# Peripherals_Main_Board.net
KiCad netlist of a schematic drawn in Altium Designer
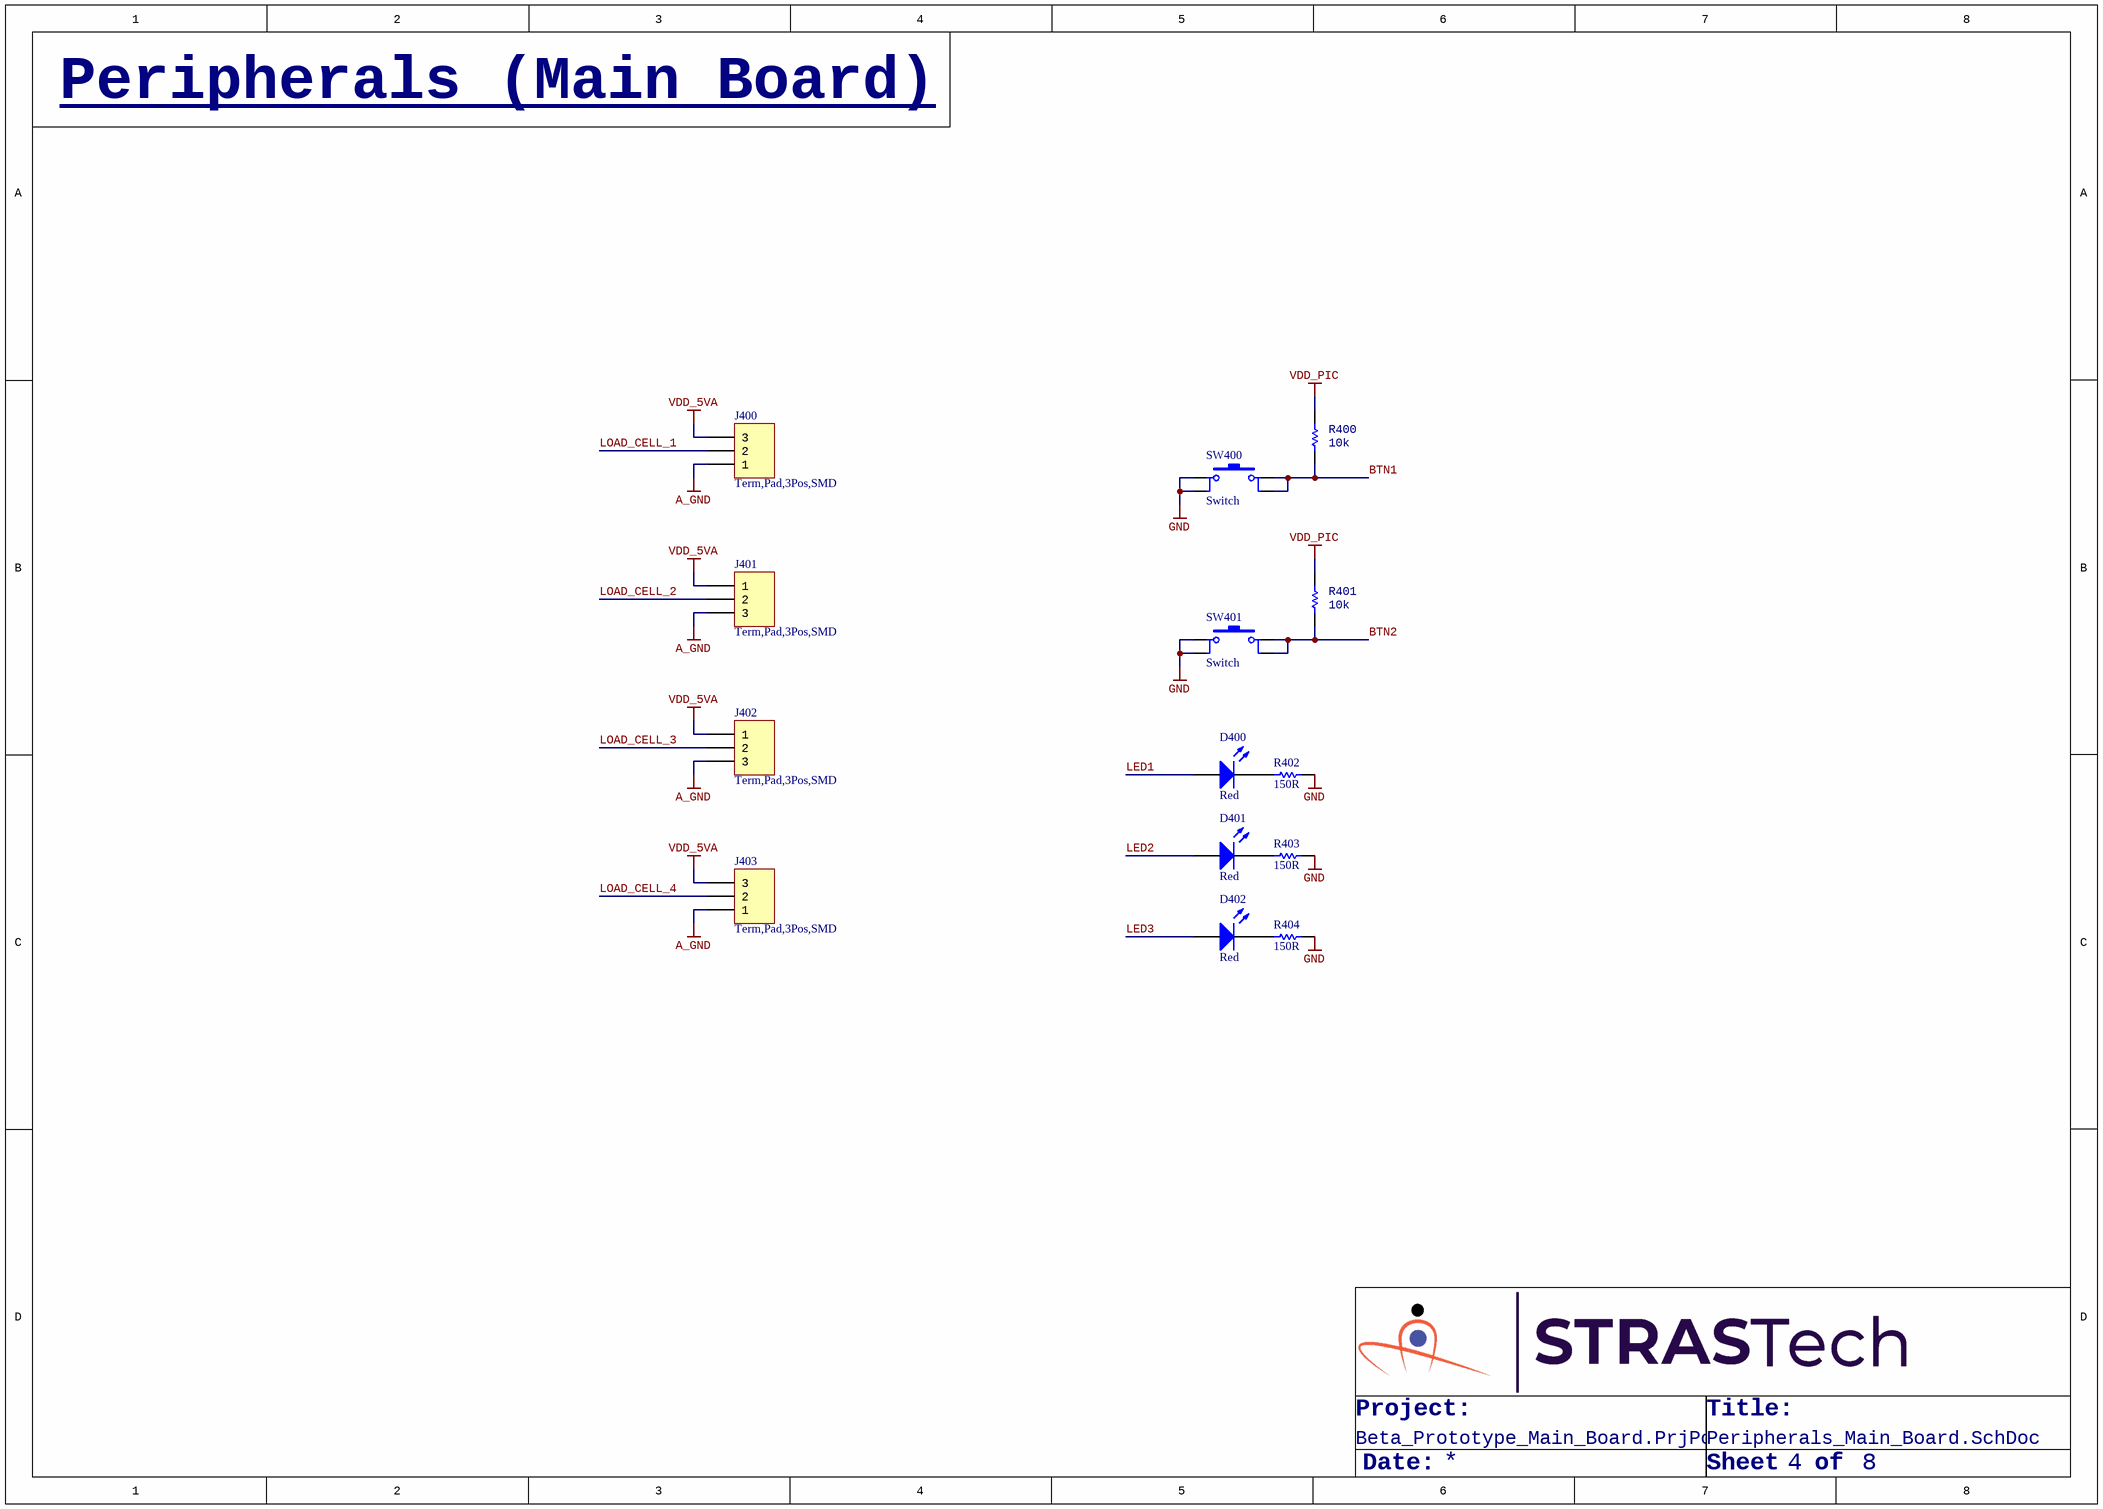
[diagram p0: Peripherals_Main_Board.SchDoc]

(export (version "E")
  (design (tool "Eeschema 10.0.6"))
  (components
    (comp (ref "D400")
      (value "Red")
      (footprint "LED,5mm,Thru")
      (description "Red 623nm LED Indication - Discrete 2V Radial")
      (fields
        (field (name "MANUFACTURER") "TT Electronics/Optek Technology")
        (field (name "MANUFACTURER PART NUMBER") "OVLFR3C7")
        (field (name "CREATEDBY") "Judd Foster")
      )
      (libsource (lib "symbols") (part "LED,Red,5mm,Thru"))
    )
    (comp (ref "D401")
      (value "Red")
      (footprint "LED,5mm,Thru")
      (description "Red 623nm LED Indication - Discrete 2V Radial")
      (fields
        (field (name "MANUFACTURER") "TT Electronics/Optek Technology")
        (field (name "MANUFACTURER PART NUMBER") "OVLFR3C7")
        (field (name "CREATEDBY") "Judd Foster")
      )
      (libsource (lib "symbols") (part "LED,Red,5mm,Thru"))
    )
    (comp (ref "D402")
      (value "Red")
      (footprint "LED,5mm,Thru")
      (description "Red 623nm LED Indication - Discrete 2V Radial")
      (fields
        (field (name "MANUFACTURER") "TT Electronics/Optek Technology")
        (field (name "MANUFACTURER PART NUMBER") "OVLFR3C7")
        (field (name "CREATEDBY") "Judd Foster")
      )
      (libsource (lib "symbols") (part "LED,Red,5mm,Thru"))
    )
    (comp (ref "J400")
      (value "Term,Pad,3Pos,SMD")
      (footprint "Term,Pad,3Pos,SMD")
      (description "SMD pads for soldering wires with strain relief")
      (fields (field (name "CREATED BY") "Judd Foster"))
      (libsource (lib "") (part "Term,Pad,3Pos,SMD_1"))
    )
    (comp (ref "J401")
      (value "Term,Pad,3Pos,SMD")
      (footprint "Term,Pad,3Pos,SMD")
      (description "SMD pads for soldering wires with strain relief")
      (fields (field (name "CREATED BY") "Judd Foster"))
      (libsource (lib "symbols") (part "Term,Pad,3Pos,SMD"))
    )
    (comp (ref "J402")
      (value "Term,Pad,3Pos,SMD")
      (footprint "Term,Pad,3Pos,SMD")
      (description "SMD pads for soldering wires with strain relief")
      (fields (field (name "CREATED BY") "Judd Foster"))
      (libsource (lib "symbols") (part "Term,Pad,3Pos,SMD"))
    )
    (comp (ref "J403")
      (value "Term,Pad,3Pos,SMD")
      (footprint "Term,Pad,3Pos,SMD")
      (description "SMD pads for soldering wires with strain relief")
      (fields (field (name "CREATED BY") "Judd Foster"))
      (libsource (lib "") (part "Term,Pad,3Pos,SMD_1"))
    )
    (comp (ref "R400")
      (value "10k")
      (footprint "RES,0402")
      (description "10 kOhms ±5% 0.063W, 1/16W Chip Resistor 0402 (1005 Metric) Automotive AEC-Q200 Thick Film")
      (fields
        (field (name "VENDOR PART NUMBER") "RMCF0402JT10K0CT-ND")
        (field (name "MANUFACTURER") "Stackpole Electronics Inc")
        (field (name "CREATEDBY") "Judd Foster")
      )
      (libsource (lib "symbols") (part "RES,10k,5%,0.063W,0402"))
    )
    (comp (ref "R401")
      (value "10k")
      (footprint "RES,0402")
      (description "10 kOhms ±5% 0.063W, 1/16W Chip Resistor 0402 (1005 Metric) Automotive AEC-Q200 Thick Film")
      (fields
        (field (name "VENDOR PART NUMBER") "RMCF0402JT10K0CT-ND")
        (field (name "MANUFACTURER") "Stackpole Electronics Inc")
        (field (name "CREATEDBY") "Judd Foster")
      )
      (libsource (lib "symbols") (part "RES,10k,5%,0.063W,0402"))
    )
    (comp (ref "R402")
      (value "150R")
      (footprint "RES,0402")
      (fields
        (field (name "MANUFACTURER") "TE Connectivity Passive Product")
        (field (name "MANUFACTURER PART NUMBER") "CRGCQ0402F150R")
        (field (name "VENDOR PART NUMBER") "A129617CT-ND")
        (field (name "CREATEDBY") "Judd Foster")
      )
      (libsource (lib "symbols") (part "RES,150R,1%,0.1W,0402"))
    )
    (comp (ref "R403")
      (value "150R")
      (footprint "RES,0402")
      (fields
        (field (name "MANUFACTURER") "TE Connectivity Passive Product")
        (field (name "MANUFACTURER PART NUMBER") "CRGCQ0402F150R")
        (field (name "VENDOR PART NUMBER") "A129617CT-ND")
        (field (name "CREATEDBY") "Judd Foster")
      )
      (libsource (lib "symbols") (part "RES,150R,1%,0.1W,0402"))
    )
    (comp (ref "R404")
      (value "150R")
      (footprint "RES,0402")
      (fields
        (field (name "MANUFACTURER") "TE Connectivity Passive Product")
        (field (name "MANUFACTURER PART NUMBER") "CRGCQ0402F150R")
        (field (name "VENDOR PART NUMBER") "A129617CT-ND")
        (field (name "CREATEDBY") "Judd Foster")
      )
      (libsource (lib "symbols") (part "RES,150R,1%,0.1W,0402"))
    )
    (comp (ref "SW400")
      (value "Switch")
      (footprint "Switch,Tactile,SPST-NO,SMD")
      (description "Tactile Switch SPST-NO Top Actuated Surface Mount")
      (fields
        (field (name "MANUFACTURER") "C&K")
        (field (name "MANUFACTURER PART NUMBER") "PTS645SK50SMTR92 LFS")
        (field (name "CREATEDBY") "Judd Foster")
      )
      (libsource (lib "symbols") (part "Switch,Tactile,SPST-NO,SMD,H5.0"))
    )
    (comp (ref "SW401")
      (value "Switch")
      (footprint "Switch,Tactile,SPST-NO,SMD")
      (description "Tactile Switch SPST-NO Top Actuated Surface Mount")
      (fields
        (field (name "MANUFACTURER") "C&K")
        (field (name "MANUFACTURER PART NUMBER") "PTS645SK50SMTR92 LFS")
        (field (name "CREATEDBY") "Judd Foster")
      )
      (libsource (lib "symbols") (part "Switch,Tactile,SPST-NO,SMD,H5.0"))
    )
  )
  (nets
    (net (code "1") (name "/BTN1") (class "Default")
      (node (ref "R400") (pin "2") (pinfunction "2_2") (pintype "passive"))
      (node (ref "SW400") (pin "3") (pinfunction "3_3") (pintype "passive"))
      (node (ref "SW400") (pin "4") (pinfunction "4_4") (pintype "passive"))
    )
    (net (code "2") (name "/BTN2") (class "Default")
      (node (ref "R401") (pin "2") (pinfunction "2_2") (pintype "passive"))
      (node (ref "SW401") (pin "3") (pinfunction "3_3") (pintype "passive"))
      (node (ref "SW401") (pin "4") (pinfunction "4_4") (pintype "passive"))
    )
    (net (code "3") (name "/LED1") (class "Default")
      (node (ref "D400") (pin "1") (pinfunction "A_1") (pintype "passive"))
    )
    (net (code "4") (name "/LED2") (class "Default")
      (node (ref "D401") (pin "1") (pinfunction "A_1") (pintype "passive"))
    )
    (net (code "5") (name "/LED3") (class "Default")
      (node (ref "D402") (pin "1") (pinfunction "A_1") (pintype "passive"))
    )
    (net (code "6") (name "/LOAD_CELL_1") (class "Default")
      (node (ref "J400") (pin "2") (pinfunction "2_2") (pintype "passive"))
    )
    (net (code "7") (name "/LOAD_CELL_2") (class "Default")
      (node (ref "J401") (pin "2") (pinfunction "2_2") (pintype "passive"))
    )
    (net (code "8") (name "/LOAD_CELL_3") (class "Default")
      (node (ref "J402") (pin "2") (pinfunction "2_2") (pintype "passive"))
    )
    (net (code "9") (name "/LOAD_CELL_4") (class "Default")
      (node (ref "J403") (pin "2") (pinfunction "2_2") (pintype "passive"))
    )
    (net (code "10") (name "A_GND") (class "Default")
      (node (ref "J400") (pin "1") (pinfunction "1_1") (pintype "passive"))
      (node (ref "J401") (pin "3") (pinfunction "3_3") (pintype "passive"))
      (node (ref "J402") (pin "3") (pinfunction "3_3") (pintype "passive"))
      (node (ref "J403") (pin "1") (pinfunction "1_1") (pintype "passive"))
    )
    (net (code "11") (name "GND") (class "Default")
      (node (ref "R402") (pin "2") (pinfunction "2_2") (pintype "passive"))
      (node (ref "R403") (pin "2") (pinfunction "2_2") (pintype "passive"))
      (node (ref "R404") (pin "2") (pinfunction "2_2") (pintype "passive"))
      (node (ref "SW400") (pin "1") (pinfunction "1_1") (pintype "passive"))
      (node (ref "SW400") (pin "2") (pinfunction "2_2") (pintype "passive"))
      (node (ref "SW401") (pin "1") (pinfunction "1_1") (pintype "passive"))
      (node (ref "SW401") (pin "2") (pinfunction "2_2") (pintype "passive"))
    )
    (net (code "12") (name "Net-(D400-K)") (class "Default")
      (node (ref "D400") (pin "2") (pinfunction "K_2") (pintype "passive"))
      (node (ref "R402") (pin "1") (pinfunction "1_1") (pintype "passive"))
    )
    (net (code "13") (name "Net-(D401-K)") (class "Default")
      (node (ref "D401") (pin "2") (pinfunction "K_2") (pintype "passive"))
      (node (ref "R403") (pin "1") (pinfunction "1_1") (pintype "passive"))
    )
    (net (code "14") (name "Net-(D402-K)") (class "Default")
      (node (ref "D402") (pin "2") (pinfunction "K_2") (pintype "passive"))
      (node (ref "R404") (pin "1") (pinfunction "1_1") (pintype "passive"))
    )
    (net (code "15") (name "VDD_5VA") (class "Default")
      (node (ref "J400") (pin "3") (pinfunction "3_3") (pintype "passive"))
      (node (ref "J401") (pin "1") (pinfunction "1_1") (pintype "passive"))
      (node (ref "J402") (pin "1") (pinfunction "1_1") (pintype "passive"))
      (node (ref "J403") (pin "3") (pinfunction "3_3") (pintype "passive"))
    )
    (net (code "16") (name "VDD_PIC") (class "Default")
      (node (ref "R400") (pin "1") (pinfunction "1_1") (pintype "passive"))
      (node (ref "R401") (pin "1") (pinfunction "1_1") (pintype "passive"))
    )
  )
)
